# lmzmv0.net
KiCad netlist of a schematic drawn in EAGLE
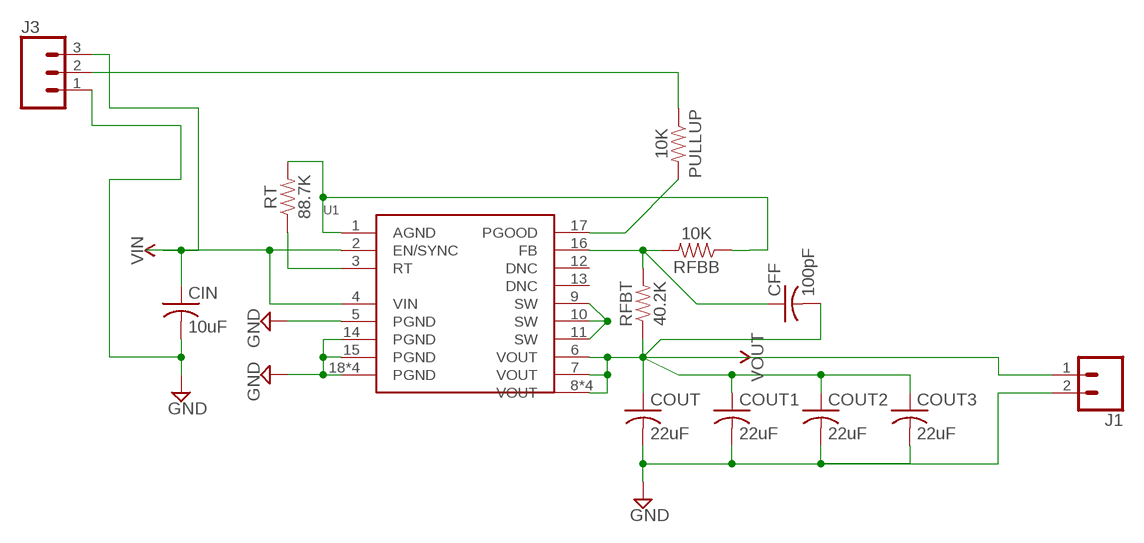
[diagram p0: schematic, sheet 1]

(export (version "E")
  (design (tool "Eeschema 10.0.6"))
  (components
    (comp (ref "CFF")
      (value "100pF")
      (footprint "eagle-import:C0603")
      (fields (field (name "MF") "YAGEO") (field (name "MPN") "CC0603JRNPO9BN101"))
      (libsource (lib "eagle-import") (part "C-USC0603"))
    )
    (comp (ref "CIN")
      (value "10uF")
      (footprint "eagle-import:C0603")
      (fields (field (name "MF") "TAIYO YUDEN") (field (name "MPN") "LMK107BJ106MALTD"))
      (libsource (lib "eagle-import") (part "C-USC0603"))
    )
    (comp (ref "COUT")
      (value "22uF")
      (footprint "eagle-import:C0603")
      (fields (field (name "MF") "AVX") (field (name "MPN") "F980G226MMA"))
      (libsource (lib "eagle-import") (part "C-USC0603"))
    )
    (comp (ref "COUT1")
      (value "22uF")
      (footprint "eagle-import:C0603")
      (fields (field (name "MF") "AVX") (field (name "MPN") "F980G226MMA"))
      (libsource (lib "eagle-import") (part "C-USC0603"))
    )
    (comp (ref "COUT2")
      (value "22uF")
      (footprint "eagle-import:C0603")
      (fields (field (name "MF") "AVX") (field (name "MPN") "F980G226MMA"))
      (libsource (lib "eagle-import") (part "C-USC0603"))
    )
    (comp (ref "COUT3")
      (value "22uF")
      (footprint "eagle-import:C0603")
      (fields (field (name "MF") "AVX") (field (name "MPN") "F980G226MMA"))
      (libsource (lib "eagle-import") (part "C-USC0603"))
    )
    (comp (ref "J1")
      (value "CONN_02")
      (footprint "eagle-import:1X02")
      (libsource (lib "eagle-import") (part "CONN_02"))
    )
    (comp (ref "J3")
      (value "CONN_031X03_NO_SILK")
      (footprint "eagle-import:1X03_NO_SILK")
      (libsource (lib "eagle-import") (part "CONN_031X03_NO_SILK"))
    )
    (comp (ref "PULLUP")
      (value "10K")
      (footprint "eagle-import:0603")
      (fields (field (name "MF") "YAGEO") (field (name "MPN") "RC0603FR-0710KL"))
      (libsource (lib "eagle-import") (part "RESISTOR0603"))
    )
    (comp (ref "RFBB")
      (value "10K")
      (footprint "eagle-import:0603")
      (fields (field (name "MF") "YAGEO") (field (name "MPN") "RC0603FR-0710KL"))
      (libsource (lib "eagle-import") (part "RESISTOR0603"))
    )
    (comp (ref "RFBT")
      (value "40.2K")
      (footprint "eagle-import:0603")
      (fields (field (name "MF") "MULTICOMP PRO") (field (name "MPN") "MC0603SAF4022T5E"))
      (libsource (lib "eagle-import") (part "RESISTOR0603"))
    )
    (comp (ref "RT")
      (value "88.7K")
      (footprint "eagle-import:0603")
      (fields (field (name "MF") "PANASONIC") (field (name "MPN") "ERJ-S03D8872V"))
      (libsource (lib "eagle-import") (part "RESISTOR0603"))
    )
    (comp (ref "U1")
      (value "LMZM_MODULEQFN18TI")
      (footprint "eagle-import:QFN-18")
      (fields (field (name "MPN") "LMZM33603RLRR"))
      (libsource (lib "eagle-import") (part "LMZM_MODULEQFN18TI"))
    )
  )
  (nets
    (net (code "1") (name "GND") (class "Default")
      (node (ref "CIN") (pin "2") (pinfunction "2_2") (pintype "passive"))
      (node (ref "COUT") (pin "2") (pinfunction "2_2") (pintype "passive"))
      (node (ref "COUT1") (pin "2") (pinfunction "2_2") (pintype "passive"))
      (node (ref "COUT2") (pin "2") (pinfunction "2_2") (pintype "passive"))
      (node (ref "COUT3") (pin "2") (pinfunction "2_2") (pintype "passive"))
      (node (ref "J1") (pin "2") (pinfunction "2_2") (pintype "passive"))
      (node (ref "J3") (pin "1") (pinfunction "1_1") (pintype "passive"))
      (node (ref "U1") (pin "14") (pinfunction "PGND_14") (pintype "power_in"))
      (node (ref "U1") (pin "15") (pinfunction "PGND_15") (pintype "power_in"))
      (node (ref "U1") (pin "18") (pinfunction "PGND_18") (pintype "power_in"))
      (node (ref "U1") (pin "5") (pinfunction "PGND_5") (pintype "power_in"))
      (node (ref "U1") (pin "W") (pinfunction "PGND_W") (pintype "power_in"))
      (node (ref "U1") (pin "W1") (pinfunction "PGND_W1") (pintype "power_in"))
      (node (ref "U1") (pin "W2") (pinfunction "PGND_W2") (pintype "power_in"))
    )
    (net (code "2") (name "Net-(J3-Pad2)") (class "Default")
      (node (ref "J3") (pin "2") (pinfunction "2_2") (pintype "passive"))
      (node (ref "PULLUP") (pin "1") (pinfunction "1_1") (pintype "passive"))
    )
    (net (code "3") (name "Net-(U1-AGND)") (class "Default")
      (node (ref "RFBB") (pin "1") (pinfunction "1_1") (pintype "passive"))
      (node (ref "RT") (pin "2") (pinfunction "2_2") (pintype "passive"))
      (node (ref "U1") (pin "1") (pinfunction "AGND_1") (pintype "power_in"))
    )
    (net (code "4") (name "Net-(U1-FB)") (class "Default")
      (node (ref "CFF") (pin "1") (pinfunction "1_1") (pintype "passive"))
      (node (ref "RFBB") (pin "2") (pinfunction "2_2") (pintype "passive"))
      (node (ref "RFBT") (pin "2") (pinfunction "2_2") (pintype "passive"))
      (node (ref "U1") (pin "16") (pinfunction "FB_16") (pintype "bidirectional"))
    )
    (net (code "5") (name "Net-(U1-PGOOD)") (class "Default")
      (node (ref "PULLUP") (pin "2") (pinfunction "2_2") (pintype "passive"))
      (node (ref "U1") (pin "17") (pinfunction "PGOOD_17") (pintype "bidirectional"))
    )
    (net (code "6") (name "Net-(U1-RT)") (class "Default")
      (node (ref "RT") (pin "1") (pinfunction "1_1") (pintype "passive"))
      (node (ref "U1") (pin "3") (pinfunction "RT_3") (pintype "bidirectional"))
    )
    (net (code "7") (name "Net-(U1-SW-Pad10)") (class "Default")
      (node (ref "U1") (pin "10") (pinfunction "SW_10") (pintype "bidirectional"))
      (node (ref "U1") (pin "11") (pinfunction "SW_11") (pintype "bidirectional"))
      (node (ref "U1") (pin "9") (pinfunction "SW_9") (pintype "bidirectional"))
    )
    (net (code "8") (name "VIN") (class "Default")
      (node (ref "CIN") (pin "1") (pinfunction "1_1") (pintype "passive"))
      (node (ref "J3") (pin "3") (pinfunction "3_3") (pintype "passive"))
      (node (ref "U1") (pin "2") (pinfunction "EN/SYNC_2") (pintype "bidirectional"))
      (node (ref "U1") (pin "4") (pinfunction "VIN_4") (pintype "input"))
    )
    (net (code "9") (name "VOUT") (class "Default")
      (node (ref "CFF") (pin "2") (pinfunction "2_2") (pintype "passive"))
      (node (ref "COUT") (pin "1") (pinfunction "1_1") (pintype "passive"))
      (node (ref "COUT1") (pin "1") (pinfunction "1_1") (pintype "passive"))
      (node (ref "COUT2") (pin "1") (pinfunction "1_1") (pintype "passive"))
      (node (ref "COUT3") (pin "1") (pinfunction "1_1") (pintype "passive"))
      (node (ref "J1") (pin "1") (pinfunction "1_1") (pintype "passive"))
      (node (ref "RFBT") (pin "1") (pinfunction "1_1") (pintype "passive"))
      (node (ref "U1") (pin "6") (pinfunction "VOUT_6") (pintype "output"))
      (node (ref "U1") (pin "7") (pinfunction "VOUT_7") (pintype "output"))
      (node (ref "U1") (pin "8") (pinfunction "VOUT_8") (pintype "output"))
      (node (ref "U1") (pin "X") (pinfunction "VOUT_X") (pintype "output"))
      (node (ref "U1") (pin "X1") (pinfunction "VOUT_X1") (pintype "output"))
      (node (ref "U1") (pin "X2") (pinfunction "VOUT_X2") (pintype "output"))
    )
    (net (code "10") (name "unconnected-(U1-DNC-Pad12)") (class "Default")
      (node (ref "U1") (pin "12") (pinfunction "DNC_12") (pintype "bidirectional"))
    )
    (net (code "11") (name "unconnected-(U1-DNC-Pad13)") (class "Default")
      (node (ref "U1") (pin "13") (pinfunction "DNC_13") (pintype "bidirectional"))
    )
  )
)
